# cell_fuses.net
KiCad netlist of a schematic drawn in Altium Designer
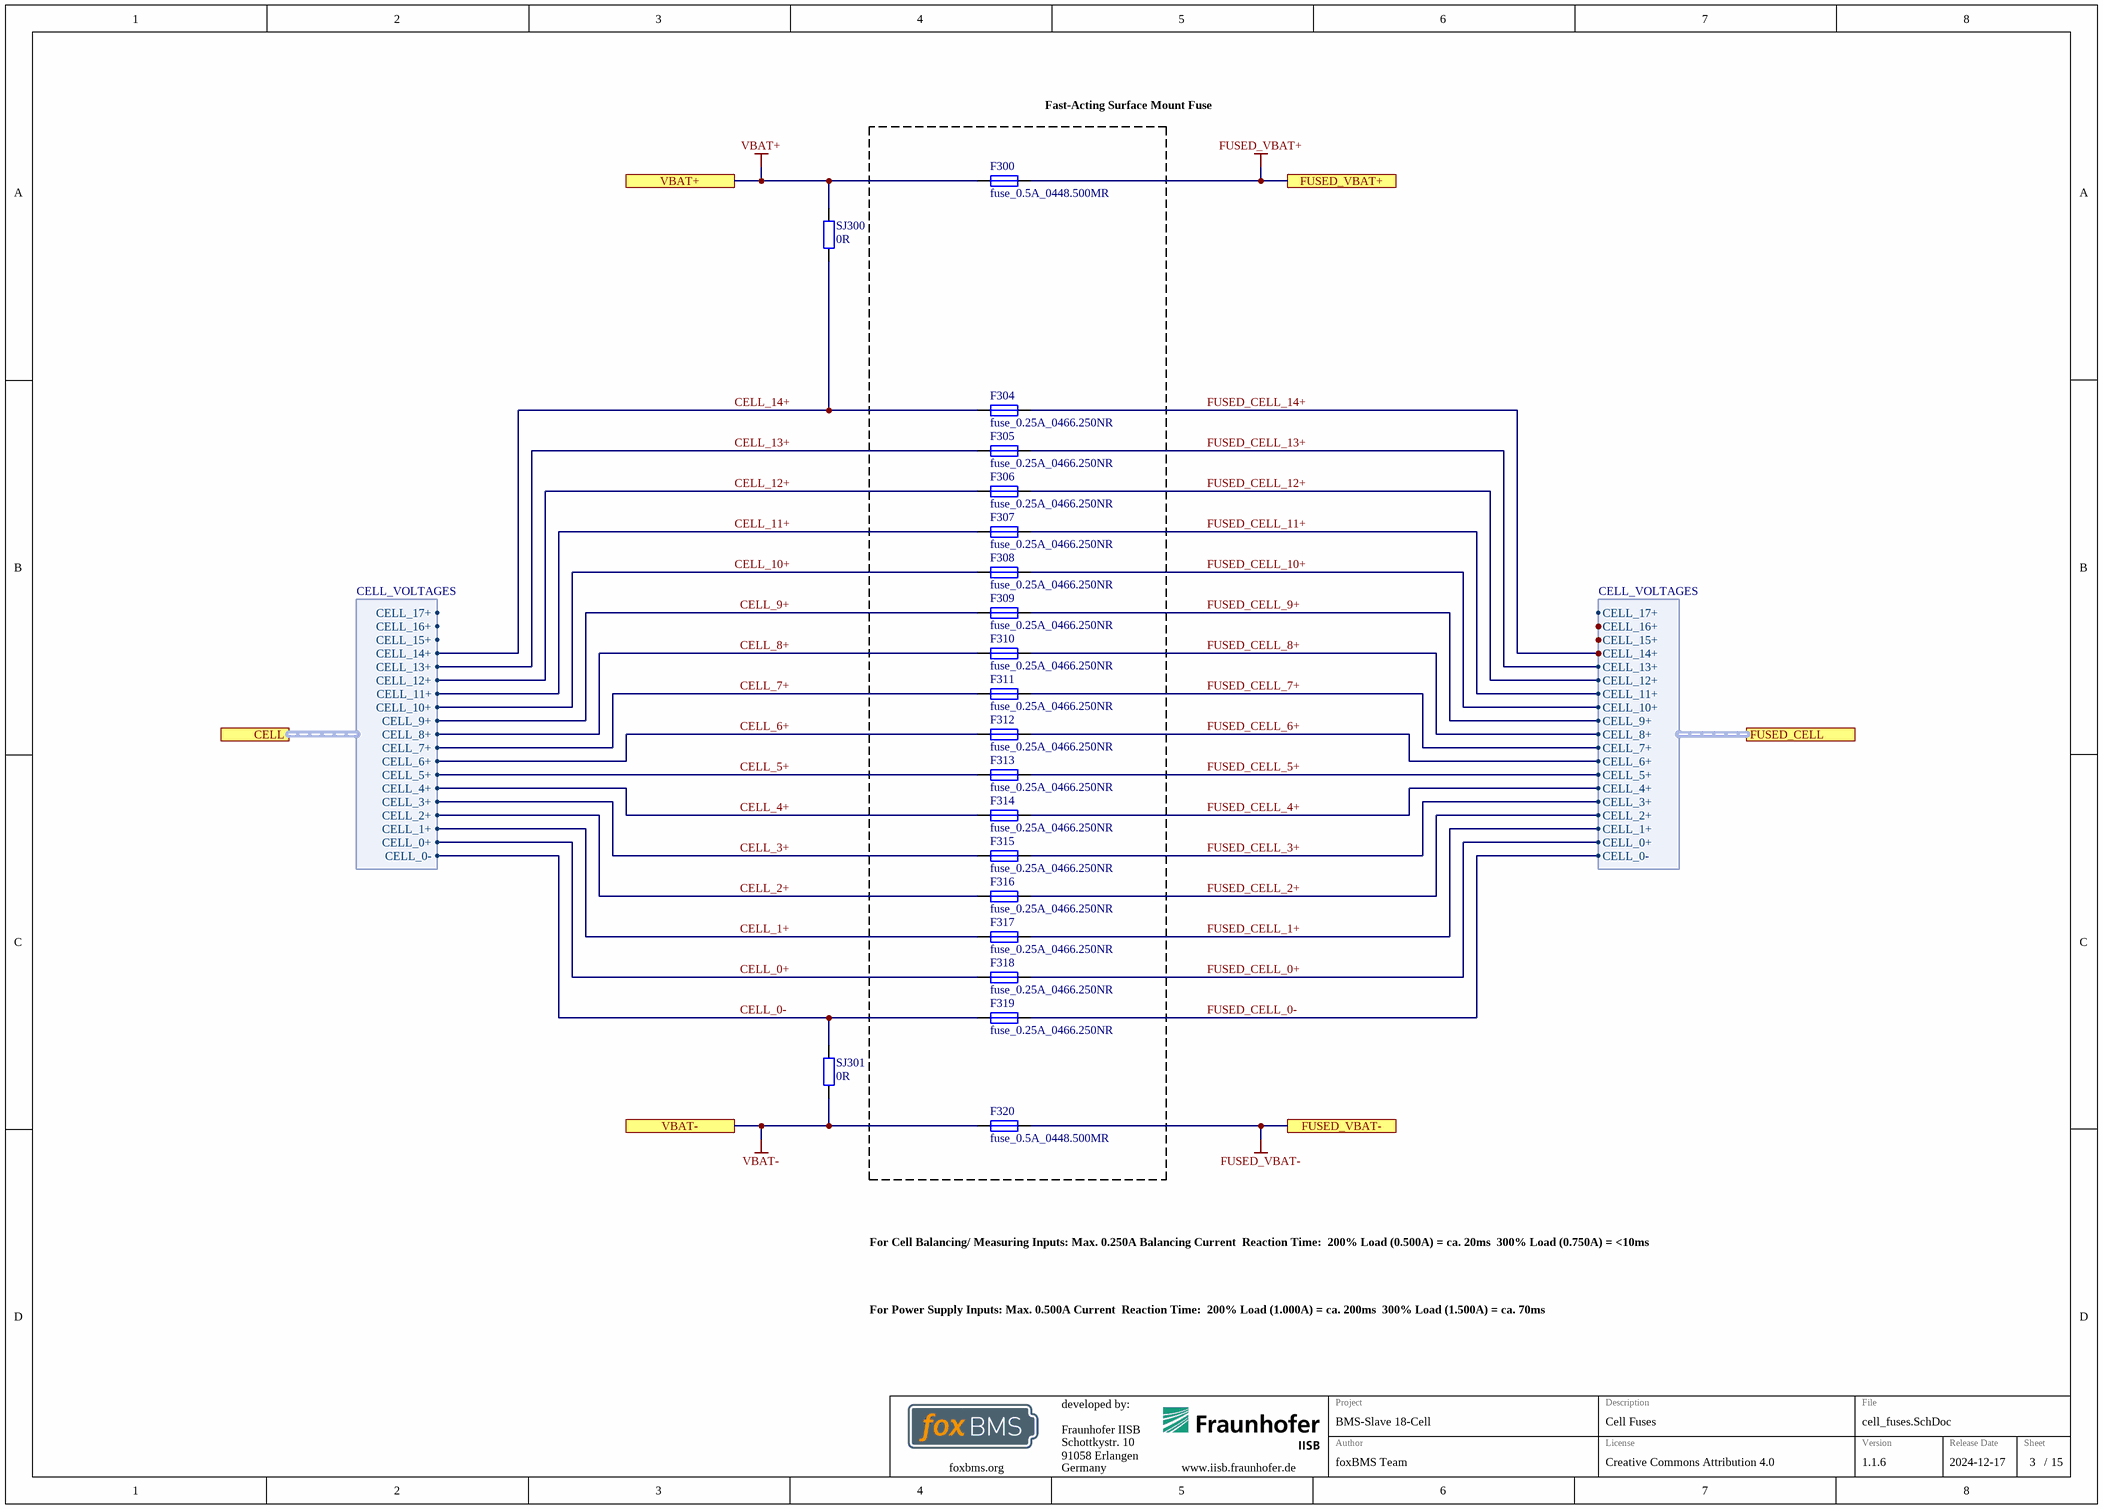
[diagram p0: cell_fuses.SchDoc]

(export (version "E")
  (design (tool "Eeschema 10.0.6"))
  (components
    (comp (ref "F300")
      (value "fuse_0.5A_0448.500MR")
      (footprint "LITTLEFUSE_448")
      (description "Fuse, Surface Mount, NANO2 Series, 500 mA, 125 VAC, 32 VDC, Very Fast Acting, SMD")
      (fields (field (name "MANUFACTURER") "Littlefuse"))
      (libsource (lib "OE750") (part "R_Fuse"))
    )
    (comp (ref "F304")
      (value "fuse_0.25A_0466.250NR")
      (footprint "LITTLEFUSE_466")
      (description "Fuse, Surface Mount, 466 Series, 250 mA, 125 VAC, 125 VDC, Very Fast Acting, 1206")
      (fields (field (name "MANUFACTURER") "Littlefuse"))
      (libsource (lib "OE750") (part "R_Fuse"))
    )
    (comp (ref "F305")
      (value "fuse_0.25A_0466.250NR")
      (footprint "LITTLEFUSE_466")
      (description "Fuse, Surface Mount, 466 Series, 250 mA, 125 VAC, 125 VDC, Very Fast Acting, 1206")
      (fields (field (name "MANUFACTURER") "Littlefuse"))
      (libsource (lib "OE750") (part "R_Fuse"))
    )
    (comp (ref "F306")
      (value "fuse_0.25A_0466.250NR")
      (footprint "LITTLEFUSE_466")
      (description "Fuse, Surface Mount, 466 Series, 250 mA, 125 VAC, 125 VDC, Very Fast Acting, 1206")
      (fields (field (name "MANUFACTURER") "Littlefuse"))
      (libsource (lib "OE750") (part "R_Fuse"))
    )
    (comp (ref "F307")
      (value "fuse_0.25A_0466.250NR")
      (footprint "LITTLEFUSE_466")
      (description "Fuse, Surface Mount, 466 Series, 250 mA, 125 VAC, 125 VDC, Very Fast Acting, 1206")
      (fields (field (name "MANUFACTURER") "Littlefuse"))
      (libsource (lib "OE750") (part "R_Fuse"))
    )
    (comp (ref "F308")
      (value "fuse_0.25A_0466.250NR")
      (footprint "LITTLEFUSE_466")
      (description "Fuse, Surface Mount, 466 Series, 250 mA, 125 VAC, 125 VDC, Very Fast Acting, 1206")
      (fields (field (name "MANUFACTURER") "Littlefuse"))
      (libsource (lib "OE750") (part "R_Fuse"))
    )
    (comp (ref "F309")
      (value "fuse_0.25A_0466.250NR")
      (footprint "LITTLEFUSE_466")
      (description "Fuse, Surface Mount, 466 Series, 250 mA, 125 VAC, 125 VDC, Very Fast Acting, 1206")
      (fields (field (name "MANUFACTURER") "Littlefuse"))
      (libsource (lib "OE750") (part "R_Fuse"))
    )
    (comp (ref "F310")
      (value "fuse_0.25A_0466.250NR")
      (footprint "LITTLEFUSE_466")
      (description "Fuse, Surface Mount, 466 Series, 250 mA, 125 VAC, 125 VDC, Very Fast Acting, 1206")
      (fields (field (name "MANUFACTURER") "Littlefuse"))
      (libsource (lib "OE750") (part "R_Fuse"))
    )
    (comp (ref "F311")
      (value "fuse_0.25A_0466.250NR")
      (footprint "LITTLEFUSE_466")
      (description "Fuse, Surface Mount, 466 Series, 250 mA, 125 VAC, 125 VDC, Very Fast Acting, 1206")
      (fields (field (name "MANUFACTURER") "Littlefuse"))
      (libsource (lib "OE750") (part "R_Fuse"))
    )
    (comp (ref "F312")
      (value "fuse_0.25A_0466.250NR")
      (footprint "LITTLEFUSE_466")
      (description "Fuse, Surface Mount, 466 Series, 250 mA, 125 VAC, 125 VDC, Very Fast Acting, 1206")
      (fields (field (name "MANUFACTURER") "Littlefuse"))
      (libsource (lib "OE750") (part "R_Fuse"))
    )
    (comp (ref "F313")
      (value "fuse_0.25A_0466.250NR")
      (footprint "LITTLEFUSE_466")
      (description "Fuse, Surface Mount, 466 Series, 250 mA, 125 VAC, 125 VDC, Very Fast Acting, 1206")
      (fields (field (name "MANUFACTURER") "Littlefuse"))
      (libsource (lib "OE750") (part "R_Fuse"))
    )
    (comp (ref "F314")
      (value "fuse_0.25A_0466.250NR")
      (footprint "LITTLEFUSE_466")
      (description "Fuse, Surface Mount, 466 Series, 250 mA, 125 VAC, 125 VDC, Very Fast Acting, 1206")
      (fields (field (name "MANUFACTURER") "Littlefuse"))
      (libsource (lib "OE750") (part "R_Fuse"))
    )
    (comp (ref "F315")
      (value "fuse_0.25A_0466.250NR")
      (footprint "LITTLEFUSE_466")
      (description "Fuse, Surface Mount, 466 Series, 250 mA, 125 VAC, 125 VDC, Very Fast Acting, 1206")
      (fields (field (name "MANUFACTURER") "Littlefuse"))
      (libsource (lib "OE750") (part "R_Fuse"))
    )
    (comp (ref "F316")
      (value "fuse_0.25A_0466.250NR")
      (footprint "LITTLEFUSE_466")
      (description "Fuse, Surface Mount, 466 Series, 250 mA, 125 VAC, 125 VDC, Very Fast Acting, 1206")
      (fields (field (name "MANUFACTURER") "Littlefuse"))
      (libsource (lib "OE750") (part "R_Fuse"))
    )
    (comp (ref "F317")
      (value "fuse_0.25A_0466.250NR")
      (footprint "LITTLEFUSE_466")
      (description "Fuse, Surface Mount, 466 Series, 250 mA, 125 VAC, 125 VDC, Very Fast Acting, 1206")
      (fields (field (name "MANUFACTURER") "Littlefuse"))
      (libsource (lib "OE750") (part "R_Fuse"))
    )
    (comp (ref "F318")
      (value "fuse_0.25A_0466.250NR")
      (footprint "LITTLEFUSE_466")
      (description "Fuse, Surface Mount, 466 Series, 250 mA, 125 VAC, 125 VDC, Very Fast Acting, 1206")
      (fields (field (name "MANUFACTURER") "Littlefuse"))
      (libsource (lib "OE750") (part "R_Fuse"))
    )
    (comp (ref "F319")
      (value "fuse_0.25A_0466.250NR")
      (footprint "LITTLEFUSE_466")
      (description "Fuse, Surface Mount, 466 Series, 250 mA, 125 VAC, 125 VDC, Very Fast Acting, 1206")
      (fields (field (name "MANUFACTURER") "Littlefuse"))
      (libsource (lib "OE750") (part "R_Fuse"))
    )
    (comp (ref "F320")
      (value "fuse_0.5A_0448.500MR")
      (footprint "LITTLEFUSE_448")
      (description "Fuse, Surface Mount, NANO2 Series, 500 mA, 125 VAC, 32 VDC, Very Fast Acting, SMD")
      (fields (field (name "MANUFACTURER") "Littlefuse"))
      (libsource (lib "OE750") (part "R_Fuse"))
    )
    (comp (ref "SJ300")
      (value "0R")
      (footprint "RESC1608X05N")
      (description "SMD Resistor 0R 0603")
      (fields (field (name "PART NUMBER") "gen_R_0R_0603") (field (name "POWER") "0.1W"))
      (libsource (lib "OE750") (part "R"))
    )
    (comp (ref "SJ301")
      (value "0R")
      (footprint "RESC1608X05N")
      (description "SMD Resistor 0R 0603")
      (fields (field (name "PART NUMBER") "gen_R_0R_0603") (field (name "POWER") "0.1W"))
      (libsource (lib "OE750") (part "R"))
    )
  )
  (nets
    (net (code "2") (name "/CELL_0+") (class "Default")
      (node (ref "F318") (pin "1") (pinfunction "1_1") (pintype "passive"))
    )
    (net (code "3") (name "/CELL_0-") (class "Default")
      (node (ref "F319") (pin "1") (pinfunction "1_1") (pintype "passive"))
      (node (ref "SJ301") (pin "1") (pinfunction "1_1") (pintype "passive"))
    )
    (net (code "4") (name "/CELL_1+") (class "Default")
      (node (ref "F317") (pin "1") (pinfunction "1_1") (pintype "passive"))
    )
    (net (code "5") (name "/CELL_2+") (class "Default")
      (node (ref "F316") (pin "1") (pinfunction "1_1") (pintype "passive"))
    )
    (net (code "6") (name "/CELL_3+") (class "Default")
      (node (ref "F315") (pin "1") (pinfunction "1_1") (pintype "passive"))
    )
    (net (code "7") (name "/CELL_4+") (class "Default")
      (node (ref "F314") (pin "1") (pinfunction "1_1") (pintype "passive"))
    )
    (net (code "8") (name "/CELL_5+") (class "Default")
      (node (ref "F313") (pin "1") (pinfunction "1_1") (pintype "passive"))
    )
    (net (code "9") (name "/CELL_6+") (class "Default")
      (node (ref "F312") (pin "1") (pinfunction "1_1") (pintype "passive"))
    )
    (net (code "10") (name "/CELL_7+") (class "Default")
      (node (ref "F311") (pin "1") (pinfunction "1_1") (pintype "passive"))
    )
    (net (code "11") (name "/CELL_8+") (class "Default")
      (node (ref "F310") (pin "1") (pinfunction "1_1") (pintype "passive"))
    )
    (net (code "12") (name "/CELL_9+") (class "Default")
      (node (ref "F309") (pin "1") (pinfunction "1_1") (pintype "passive"))
    )
    (net (code "13") (name "/CELL_10+") (class "Default")
      (node (ref "F308") (pin "1") (pinfunction "1_1") (pintype "passive"))
    )
    (net (code "14") (name "/CELL_11+") (class "Default")
      (node (ref "F307") (pin "1") (pinfunction "1_1") (pintype "passive"))
    )
    (net (code "15") (name "/CELL_12+") (class "Default")
      (node (ref "F306") (pin "1") (pinfunction "1_1") (pintype "passive"))
    )
    (net (code "16") (name "/CELL_13+") (class "Default")
      (node (ref "F305") (pin "1") (pinfunction "1_1") (pintype "passive"))
    )
    (net (code "17") (name "/CELL_14+") (class "Default")
      (node (ref "F304") (pin "1") (pinfunction "1_1") (pintype "passive"))
      (node (ref "SJ300") (pin "2") (pinfunction "2_2") (pintype "passive"))
    )
    (net (code "18") (name "/FUSED_CELL_0+") (class "Default")
      (node (ref "F318") (pin "2") (pinfunction "2_2") (pintype "passive"))
    )
    (net (code "19") (name "/FUSED_CELL_0-") (class "Default")
      (node (ref "F319") (pin "2") (pinfunction "2_2") (pintype "passive"))
    )
    (net (code "20") (name "/FUSED_CELL_1+") (class "Default")
      (node (ref "F317") (pin "2") (pinfunction "2_2") (pintype "passive"))
    )
    (net (code "21") (name "/FUSED_CELL_2+") (class "Default")
      (node (ref "F316") (pin "2") (pinfunction "2_2") (pintype "passive"))
    )
    (net (code "22") (name "/FUSED_CELL_3+") (class "Default")
      (node (ref "F315") (pin "2") (pinfunction "2_2") (pintype "passive"))
    )
    (net (code "23") (name "/FUSED_CELL_4+") (class "Default")
      (node (ref "F314") (pin "2") (pinfunction "2_2") (pintype "passive"))
    )
    (net (code "24") (name "/FUSED_CELL_5+") (class "Default")
      (node (ref "F313") (pin "2") (pinfunction "2_2") (pintype "passive"))
    )
    (net (code "25") (name "/FUSED_CELL_6+") (class "Default")
      (node (ref "F312") (pin "2") (pinfunction "2_2") (pintype "passive"))
    )
    (net (code "26") (name "/FUSED_CELL_7+") (class "Default")
      (node (ref "F311") (pin "2") (pinfunction "2_2") (pintype "passive"))
    )
    (net (code "27") (name "/FUSED_CELL_8+") (class "Default")
      (node (ref "F310") (pin "2") (pinfunction "2_2") (pintype "passive"))
    )
    (net (code "28") (name "/FUSED_CELL_9+") (class "Default")
      (node (ref "F309") (pin "2") (pinfunction "2_2") (pintype "passive"))
    )
    (net (code "29") (name "/FUSED_CELL_10+") (class "Default")
      (node (ref "F308") (pin "2") (pinfunction "2_2") (pintype "passive"))
    )
    (net (code "30") (name "/FUSED_CELL_11+") (class "Default")
      (node (ref "F307") (pin "2") (pinfunction "2_2") (pintype "passive"))
    )
    (net (code "31") (name "/FUSED_CELL_12+") (class "Default")
      (node (ref "F306") (pin "2") (pinfunction "2_2") (pintype "passive"))
    )
    (net (code "32") (name "/FUSED_CELL_13+") (class "Default")
      (node (ref "F305") (pin "2") (pinfunction "2_2") (pintype "passive"))
    )
    (net (code "33") (name "/FUSED_CELL_14+") (class "Default")
      (node (ref "F304") (pin "2") (pinfunction "2_2") (pintype "passive"))
    )
    (net (code "35") (name "FUSED_VBAT+") (class "Default")
      (node (ref "F300") (pin "2") (pinfunction "2_2") (pintype "passive"))
    )
    (net (code "36") (name "FUSED_VBAT-") (class "Default")
      (node (ref "F320") (pin "2") (pinfunction "2_2") (pintype "passive"))
    )
    (net (code "37") (name "VBAT+") (class "Default")
      (node (ref "F300") (pin "1") (pinfunction "1_1") (pintype "passive"))
      (node (ref "SJ300") (pin "1") (pinfunction "1_1") (pintype "passive"))
    )
    (net (code "38") (name "VBAT-") (class "Default")
      (node (ref "F320") (pin "1") (pinfunction "1_1") (pintype "passive"))
      (node (ref "SJ301") (pin "2") (pinfunction "2_2") (pintype "passive"))
    )
  )
)
